# VM_Motor_v06.net
KiCad netlist of a schematic drawn in EAGLE
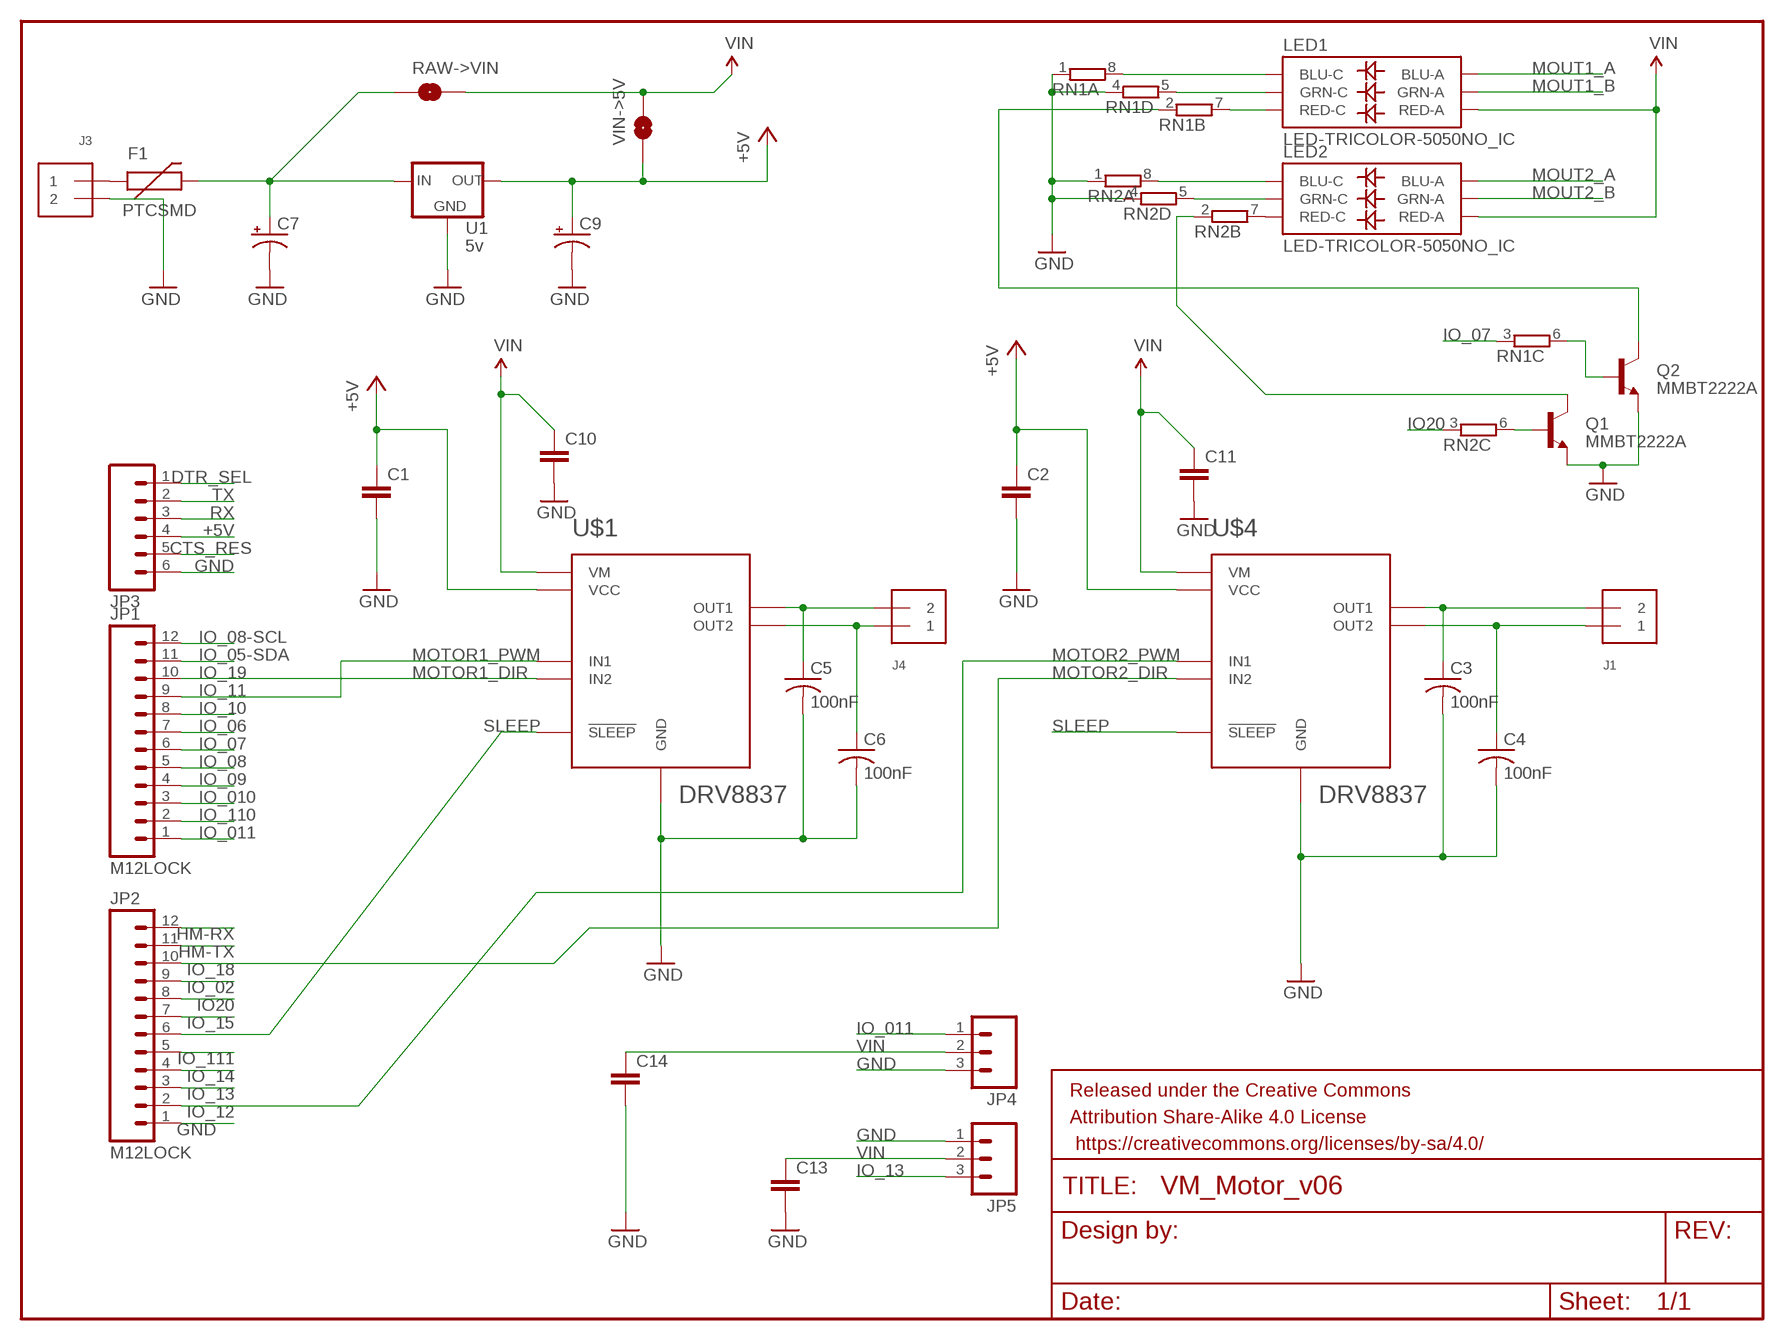
[diagram p0: schematic, sheet 1]

(export (version "E")
  (design (tool "Eeschema 10.0.6"))
  (components
    (comp (ref "C1")
      (value "CAP0402-CAP")
      (footprint "eagle-import:0402-CAP")
      (libsource (lib "eagle-import") (part "CAP0402-CAP"))
    )
    (comp (ref "C2")
      (value "CAP0402-CAP")
      (footprint "eagle-import:0402-CAP")
      (libsource (lib "eagle-import") (part "CAP0402-CAP"))
    )
    (comp (ref "C3")
      (value "100nF")
      (footprint "eagle-import:C0402")
      (libsource (lib "eagle-import") (part "C-USC0402"))
    )
    (comp (ref "C4")
      (value "100nF")
      (footprint "eagle-import:C0402")
      (libsource (lib "eagle-import") (part "C-USC0402"))
    )
    (comp (ref "C5")
      (value "100nF")
      (footprint "eagle-import:C0402")
      (libsource (lib "eagle-import") (part "C-USC0402"))
    )
    (comp (ref "C6")
      (value "100nF")
      (footprint "eagle-import:C0402")
      (libsource (lib "eagle-import") (part "C-USC0402"))
    )
    (comp (ref "C7")
      (value "CPOL-US150CLZ-0810")
      (footprint "eagle-import:150CLZ-0810")
      (libsource (lib "eagle-import") (part "CPOL-US150CLZ-0810"))
    )
    (comp (ref "C9")
      (value "CPOL-US150CLZ-0810")
      (footprint "eagle-import:150CLZ-0810")
      (libsource (lib "eagle-import") (part "CPOL-US150CLZ-0810"))
    )
    (comp (ref "C10")
      (value "CAP0402-CAP")
      (footprint "eagle-import:0402-CAP")
      (libsource (lib "eagle-import") (part "CAP0402-CAP"))
    )
    (comp (ref "C11")
      (value "CAP0402-CAP")
      (footprint "eagle-import:0402-CAP")
      (libsource (lib "eagle-import") (part "CAP0402-CAP"))
    )
    (comp (ref "C13")
      (value "CAP0402-CAP")
      (footprint "eagle-import:0402-CAP")
      (libsource (lib "eagle-import") (part "CAP0402-CAP"))
    )
    (comp (ref "C14")
      (value "CAP0402-CAP")
      (footprint "eagle-import:0402-CAP")
      (libsource (lib "eagle-import") (part "CAP0402-CAP"))
    )
    (comp (ref "F1")
      (value "PTCSMD")
      (footprint "eagle-import:PTC-1206")
      (libsource (lib "eagle-import") (part "PTCSMD"))
    )
    (comp (ref "FRAME1")
      (value "FRAME-LETTER")
      (footprint "eagle-import:CREATIVE_COMMONS")
      (libsource (lib "eagle-import") (part "FRAME-LETTER"))
    )
    (comp (ref "J1")
      (value "TERMBLOCK_1X2")
      (footprint "eagle-import:TERMBLOCK_1X2-3.5MM")
      (libsource (lib "eagle-import") (part "TERMBLOCK_1X2"))
    )
    (comp (ref "J3")
      (value "TERMBLOCK_1X2")
      (footprint "eagle-import:TERMBLOCK_1X2-3.5MM")
      (libsource (lib "eagle-import") (part "TERMBLOCK_1X2"))
    )
    (comp (ref "J4")
      (value "TERMBLOCK_1X2")
      (footprint "eagle-import:TERMBLOCK_1X2-3.5MM")
      (libsource (lib "eagle-import") (part "TERMBLOCK_1X2"))
    )
    (comp (ref "JP1")
      (value "M12LOCK")
      (footprint "eagle-import:1X12_LOCK")
      (libsource (lib "eagle-import") (part "M12LOCK"))
    )
    (comp (ref "JP2")
      (value "M12LOCK")
      (footprint "eagle-import:1X12_LOCK")
      (libsource (lib "eagle-import") (part "M12LOCK"))
    )
    (comp (ref "JP3")
      (value "M06LOCK")
      (footprint "eagle-import:1X06_LOCK")
      (libsource (lib "eagle-import") (part "M06LOCK"))
    )
    (comp (ref "JP4")
      (value "M03LOCK")
      (footprint "eagle-import:1X03_LOCK")
      (libsource (lib "eagle-import") (part "M03LOCK"))
    )
    (comp (ref "JP5")
      (value "M03LOCK")
      (footprint "eagle-import:1X03_LOCK")
      (libsource (lib "eagle-import") (part "M03LOCK"))
    )
    (comp (ref "LED1")
      (value "LED-TRICOLOR-5050NO_IC")
      (footprint "eagle-import:LED-TRICOLOR-5050")
      (libsource (lib "eagle-import") (part "LED-TRICOLOR-5050NO_IC"))
    )
    (comp (ref "LED2")
      (value "LED-TRICOLOR-5050NO_IC")
      (footprint "eagle-import:LED-TRICOLOR-5050")
      (libsource (lib "eagle-import") (part "LED-TRICOLOR-5050NO_IC"))
    )
    (comp (ref "Q1")
      (value "MMBT2222A")
      (footprint "eagle-import:SOT23-3")
      (libsource (lib "eagle-import") (part "TRANSISTOR_NPNMMBT2222A"))
    )
    (comp (ref "Q2")
      (value "MMBT2222A")
      (footprint "eagle-import:SOT23-3")
      (libsource (lib "eagle-import") (part "TRANSISTOR_NPNMMBT2222A"))
    )
    (comp (ref "RAW->VIN")
      (value "SOLDERJUMPERNO")
      (footprint "eagle-import:SJ_2S-NO")
      (libsource (lib "eagle-import") (part "SOLDERJUMPERNO"))
    )
    (comp (ref "RN1")
      (value "4R-N0402ARV341")
      (footprint "eagle-import:4X0402ARV341")
      (libsource (lib "eagle-import") (part "4R-N0402ARV341"))
    )
    (comp (ref "RN2")
      (value "4R-N0402ARV341")
      (footprint "eagle-import:4X0402ARV341")
      (libsource (lib "eagle-import") (part "4R-N0402ARV341"))
    )
    (comp (ref "U$1")
      (value "DRV8837")
      (footprint "eagle-import:QFN8")
      (libsource (lib "eagle-import") (part "DRV8837"))
    )
    (comp (ref "U$4")
      (value "DRV8837")
      (footprint "eagle-import:QFN8")
      (libsource (lib "eagle-import") (part "DRV8837"))
    )
    (comp (ref "U1")
      (value "5v")
      (footprint "eagle-import:DPAK")
      (libsource (lib "eagle-import") (part "V_REG_MC33269DT"))
    )
    (comp (ref "VIN->5V")
      (value "SOLDERJUMPERNO")
      (footprint "eagle-import:SJ_2S-NO")
      (libsource (lib "eagle-import") (part "SOLDERJUMPERNO"))
    )
  )
  (nets
    (net (code "1") (name "+5V") (class "Default")
      (node (ref "C1") (pin "1") (pinfunction "1_1") (pintype "passive"))
      (node (ref "C2") (pin "1") (pinfunction "1_1") (pintype "passive"))
      (node (ref "C9") (pin "+") (pinfunction "+_+") (pintype "passive"))
      (node (ref "JP3") (pin "4") (pinfunction "4_4") (pintype "passive"))
      (node (ref "U$1") (pin "P$8") (pinfunction "VCC_P$8") (pintype "bidirectional"))
      (node (ref "U$4") (pin "P$8") (pinfunction "VCC_P$8") (pintype "bidirectional"))
      (node (ref "U1") (pin "4") (pinfunction "OUT_4") (pintype "output"))
      (node (ref "VIN->5V") (pin "1") (pinfunction "1_1") (pintype "passive"))
    )
    (net (code "2") (name "/CTS_RES") (class "Default")
      (node (ref "JP3") (pin "5") (pinfunction "5_5") (pintype "passive"))
    )
    (net (code "3") (name "/DTR_SEL") (class "Default")
      (node (ref "JP3") (pin "1") (pinfunction "1_1") (pintype "passive"))
    )
    (net (code "4") (name "/HM-RX") (class "Default")
      (node (ref "JP2") (pin "12") (pinfunction "12_12") (pintype "passive"))
    )
    (net (code "5") (name "/HM-TX") (class "Default")
      (node (ref "JP2") (pin "11") (pinfunction "11_11") (pintype "passive"))
    )
    (net (code "6") (name "/IO20") (class "Default")
      (node (ref "JP2") (pin "8") (pinfunction "8_8") (pintype "passive"))
      (node (ref "RN2") (pin "3") (pinfunction "1_3") (pintype "passive"))
    )
    (net (code "7") (name "/IO_02") (class "Default")
      (node (ref "JP2") (pin "9") (pinfunction "9_9") (pintype "passive"))
    )
    (net (code "8") (name "/IO_05-SDA") (class "Default")
      (node (ref "JP1") (pin "11") (pinfunction "11_11") (pintype "passive"))
    )
    (net (code "9") (name "/IO_06") (class "Default")
      (node (ref "JP1") (pin "7") (pinfunction "7_7") (pintype "passive"))
    )
    (net (code "10") (name "/IO_07") (class "Default")
      (node (ref "JP1") (pin "6") (pinfunction "6_6") (pintype "passive"))
      (node (ref "RN1") (pin "3") (pinfunction "1_3") (pintype "passive"))
    )
    (net (code "11") (name "/IO_08") (class "Default")
      (node (ref "JP1") (pin "5") (pinfunction "5_5") (pintype "passive"))
    )
    (net (code "12") (name "/IO_08-SCL") (class "Default")
      (node (ref "JP1") (pin "12") (pinfunction "12_12") (pintype "passive"))
    )
    (net (code "13") (name "/IO_09") (class "Default")
      (node (ref "JP1") (pin "4") (pinfunction "4_4") (pintype "passive"))
    )
    (net (code "14") (name "/IO_10") (class "Default")
      (node (ref "JP1") (pin "8") (pinfunction "8_8") (pintype "passive"))
    )
    (net (code "15") (name "/IO_010") (class "Default")
      (node (ref "JP1") (pin "3") (pinfunction "3_3") (pintype "passive"))
    )
    (net (code "16") (name "/IO_011") (class "Default")
      (node (ref "JP1") (pin "1") (pinfunction "1_1") (pintype "passive"))
      (node (ref "JP4") (pin "1") (pinfunction "1_1") (pintype "passive"))
    )
    (net (code "17") (name "/IO_13") (class "Default")
      (node (ref "JP2") (pin "3") (pinfunction "3_3") (pintype "passive"))
      (node (ref "JP5") (pin "3") (pinfunction "3_3") (pintype "passive"))
    )
    (net (code "18") (name "/IO_14") (class "Default")
      (node (ref "JP2") (pin "4") (pinfunction "4_4") (pintype "passive"))
    )
    (net (code "19") (name "/IO_15") (class "Default")
      (node (ref "JP2") (pin "7") (pinfunction "7_7") (pintype "passive"))
    )
    (net (code "20") (name "/IO_110") (class "Default")
      (node (ref "JP1") (pin "2") (pinfunction "2_2") (pintype "passive"))
    )
    (net (code "21") (name "/IO_111") (class "Default")
      (node (ref "JP2") (pin "5") (pinfunction "5_5") (pintype "passive"))
    )
    (net (code "22") (name "/MOTOR1_DIR") (class "Default")
      (node (ref "JP1") (pin "10") (pinfunction "10_10") (pintype "passive"))
      (node (ref "U$1") (pin "P$5") (pinfunction "IN2_P$5") (pintype "bidirectional"))
    )
    (net (code "23") (name "/MOTOR1_PWM") (class "Default")
      (node (ref "JP1") (pin "9") (pinfunction "9_9") (pintype "passive"))
      (node (ref "U$1") (pin "P$6") (pinfunction "IN1_P$6") (pintype "bidirectional"))
    )
    (net (code "24") (name "/MOTOR2_DIR") (class "Default")
      (node (ref "JP2") (pin "10") (pinfunction "10_10") (pintype "passive"))
      (node (ref "U$4") (pin "P$5") (pinfunction "IN2_P$5") (pintype "bidirectional"))
    )
    (net (code "25") (name "/MOTOR2_PWM") (class "Default")
      (node (ref "JP2") (pin "2") (pinfunction "2_2") (pintype "passive"))
      (node (ref "U$4") (pin "P$6") (pinfunction "IN1_P$6") (pintype "bidirectional"))
    )
    (net (code "26") (name "/MOUT1_A") (class "Default")
      (node (ref "C5") (pin "1") (pinfunction "1_1") (pintype "passive"))
      (node (ref "J4") (pin "2") (pinfunction "2_2") (pintype "passive"))
      (node (ref "LED1") (pin "3") (pinfunction "BLU-A_3") (pintype "bidirectional"))
      (node (ref "U$1") (pin "P$2") (pinfunction "OUT1_P$2") (pintype "bidirectional"))
    )
    (net (code "27") (name "/MOUT1_B") (class "Default")
      (node (ref "C6") (pin "1") (pinfunction "1_1") (pintype "passive"))
      (node (ref "J4") (pin "1") (pinfunction "1_1") (pintype "passive"))
      (node (ref "LED1") (pin "1") (pinfunction "GRN-A_1") (pintype "bidirectional"))
      (node (ref "U$1") (pin "P$3") (pinfunction "OUT2_P$3") (pintype "bidirectional"))
    )
    (net (code "28") (name "/MOUT2_A") (class "Default")
      (node (ref "C3") (pin "1") (pinfunction "1_1") (pintype "passive"))
      (node (ref "J1") (pin "2") (pinfunction "2_2") (pintype "passive"))
      (node (ref "LED2") (pin "3") (pinfunction "BLU-A_3") (pintype "bidirectional"))
      (node (ref "U$4") (pin "P$2") (pinfunction "OUT1_P$2") (pintype "bidirectional"))
    )
    (net (code "29") (name "/MOUT2_B") (class "Default")
      (node (ref "C4") (pin "1") (pinfunction "1_1") (pintype "passive"))
      (node (ref "J1") (pin "1") (pinfunction "1_1") (pintype "passive"))
      (node (ref "LED2") (pin "1") (pinfunction "GRN-A_1") (pintype "bidirectional"))
      (node (ref "U$4") (pin "P$3") (pinfunction "OUT2_P$3") (pintype "bidirectional"))
    )
    (net (code "30") (name "/RX") (class "Default")
      (node (ref "JP3") (pin "3") (pinfunction "3_3") (pintype "passive"))
    )
    (net (code "31") (name "/SLEEP") (class "Default")
      (node (ref "JP2") (pin "6") (pinfunction "6_6") (pintype "passive"))
      (node (ref "U$1") (pin "P$7") (pinfunction "~{SLEEP}_P$7") (pintype "bidirectional"))
      (node (ref "U$4") (pin "P$7") (pinfunction "~{SLEEP}_P$7") (pintype "bidirectional"))
    )
    (net (code "32") (name "/TX") (class "Default")
      (node (ref "JP3") (pin "2") (pinfunction "2_2") (pintype "passive"))
    )
    (net (code "33") (name "GND") (class "Default")
      (node (ref "C1") (pin "2") (pinfunction "2_2") (pintype "passive"))
      (node (ref "C10") (pin "2") (pinfunction "2_2") (pintype "passive"))
      (node (ref "C11") (pin "2") (pinfunction "2_2") (pintype "passive"))
      (node (ref "C13") (pin "2") (pinfunction "2_2") (pintype "passive"))
      (node (ref "C14") (pin "2") (pinfunction "2_2") (pintype "passive"))
      (node (ref "C2") (pin "2") (pinfunction "2_2") (pintype "passive"))
      (node (ref "C3") (pin "2") (pinfunction "2_2") (pintype "passive"))
      (node (ref "C4") (pin "2") (pinfunction "2_2") (pintype "passive"))
      (node (ref "C5") (pin "2") (pinfunction "2_2") (pintype "passive"))
      (node (ref "C6") (pin "2") (pinfunction "2_2") (pintype "passive"))
      (node (ref "C7") (pin "-") (pinfunction "-_-") (pintype "passive"))
      (node (ref "C9") (pin "-") (pinfunction "-_-") (pintype "passive"))
      (node (ref "J3") (pin "2") (pinfunction "2_2") (pintype "passive"))
      (node (ref "JP2") (pin "1") (pinfunction "1_1") (pintype "passive"))
      (node (ref "JP3") (pin "6") (pinfunction "6_6") (pintype "passive"))
      (node (ref "JP4") (pin "3") (pinfunction "3_3") (pintype "passive"))
      (node (ref "JP5") (pin "1") (pinfunction "1_1") (pintype "passive"))
      (node (ref "Q1") (pin "2") (pinfunction "E_2") (pintype "passive"))
      (node (ref "Q2") (pin "2") (pinfunction "E_2") (pintype "passive"))
      (node (ref "RN1") (pin "1") (pinfunction "1_1") (pintype "passive"))
      (node (ref "RN1") (pin "4") (pinfunction "1_4") (pintype "passive"))
      (node (ref "RN2") (pin "1") (pinfunction "1_1") (pintype "passive"))
      (node (ref "RN2") (pin "4") (pinfunction "1_4") (pintype "passive"))
      (node (ref "U$1") (pin "P$10") (pinfunction "GND_P$10") (pintype "bidirectional"))
      (node (ref "U$1") (pin "P$11") (pinfunction "GND_P$11") (pintype "bidirectional"))
      (node (ref "U$1") (pin "P$4") (pinfunction "GND_P$4") (pintype "bidirectional"))
      (node (ref "U$1") (pin "P$9") (pinfunction "GND_P$9") (pintype "bidirectional"))
      (node (ref "U$4") (pin "P$10") (pinfunction "GND_P$10") (pintype "bidirectional"))
      (node (ref "U$4") (pin "P$11") (pinfunction "GND_P$11") (pintype "bidirectional"))
      (node (ref "U$4") (pin "P$4") (pinfunction "GND_P$4") (pintype "bidirectional"))
      (node (ref "U$4") (pin "P$9") (pinfunction "GND_P$9") (pintype "bidirectional"))
      (node (ref "U1") (pin "1") (pinfunction "GND_1") (pintype "input"))
    )
    (net (code "34") (name "Net-(F1-Pad1)") (class "Default")
      (node (ref "F1") (pin "1") (pinfunction "1_1") (pintype "bidirectional"))
      (node (ref "J3") (pin "1") (pinfunction "1_1") (pintype "passive"))
    )
    (net (code "35") (name "Net-(LED1-BLU-C)") (class "Default")
      (node (ref "LED1") (pin "4") (pinfunction "BLU-C_4") (pintype "bidirectional"))
      (node (ref "RN1") (pin "8") (pinfunction "2_8") (pintype "passive"))
    )
    (net (code "36") (name "Net-(LED1-GRN-C)") (class "Default")
      (node (ref "LED1") (pin "6") (pinfunction "GRN-C_6") (pintype "bidirectional"))
      (node (ref "RN1") (pin "5") (pinfunction "2_5") (pintype "passive"))
    )
    (net (code "37") (name "Net-(LED1-RED-C)") (class "Default")
      (node (ref "LED1") (pin "5") (pinfunction "RED-C_5") (pintype "bidirectional"))
      (node (ref "RN1") (pin "7") (pinfunction "2_7") (pintype "passive"))
    )
    (net (code "38") (name "Net-(LED2-BLU-C)") (class "Default")
      (node (ref "LED2") (pin "4") (pinfunction "BLU-C_4") (pintype "bidirectional"))
      (node (ref "RN2") (pin "8") (pinfunction "2_8") (pintype "passive"))
    )
    (net (code "39") (name "Net-(LED2-GRN-C)") (class "Default")
      (node (ref "LED2") (pin "6") (pinfunction "GRN-C_6") (pintype "bidirectional"))
      (node (ref "RN2") (pin "5") (pinfunction "2_5") (pintype "passive"))
    )
    (net (code "40") (name "Net-(LED2-RED-C)") (class "Default")
      (node (ref "LED2") (pin "5") (pinfunction "RED-C_5") (pintype "bidirectional"))
      (node (ref "RN2") (pin "7") (pinfunction "2_7") (pintype "passive"))
    )
    (net (code "41") (name "Net-(Q1-B)") (class "Default")
      (node (ref "Q1") (pin "1") (pinfunction "B_1") (pintype "passive"))
      (node (ref "RN2") (pin "6") (pinfunction "2_6") (pintype "passive"))
    )
    (net (code "42") (name "Net-(Q1-C)") (class "Default")
      (node (ref "Q1") (pin "3") (pinfunction "C_3") (pintype "passive"))
      (node (ref "RN2") (pin "2") (pinfunction "1_2") (pintype "passive"))
    )
    (net (code "43") (name "Net-(Q2-B)") (class "Default")
      (node (ref "Q2") (pin "1") (pinfunction "B_1") (pintype "passive"))
      (node (ref "RN1") (pin "6") (pinfunction "2_6") (pintype "passive"))
    )
    (net (code "44") (name "Net-(Q2-C)") (class "Default")
      (node (ref "Q2") (pin "3") (pinfunction "C_3") (pintype "passive"))
      (node (ref "RN1") (pin "2") (pinfunction "1_2") (pintype "passive"))
    )
    (net (code "45") (name "Net-(U1-IN)") (class "Default")
      (node (ref "C7") (pin "+") (pinfunction "+_+") (pintype "passive"))
      (node (ref "F1") (pin "2") (pinfunction "2_2") (pintype "bidirectional"))
      (node (ref "RAW->VIN") (pin "1") (pinfunction "1_1") (pintype "passive"))
      (node (ref "U1") (pin "3") (pinfunction "IN_3") (pintype "input"))
    )
    (net (code "46") (name "VIN") (class "Default")
      (node (ref "C10") (pin "1") (pinfunction "1_1") (pintype "passive"))
      (node (ref "C11") (pin "1") (pinfunction "1_1") (pintype "passive"))
      (node (ref "C13") (pin "1") (pinfunction "1_1") (pintype "passive"))
      (node (ref "C14") (pin "1") (pinfunction "1_1") (pintype "passive"))
      (node (ref "JP4") (pin "2") (pinfunction "2_2") (pintype "passive"))
      (node (ref "JP5") (pin "2") (pinfunction "2_2") (pintype "passive"))
      (node (ref "LED1") (pin "2") (pinfunction "RED-A_2") (pintype "bidirectional"))
      (node (ref "LED2") (pin "2") (pinfunction "RED-A_2") (pintype "bidirectional"))
      (node (ref "RAW->VIN") (pin "2") (pinfunction "2_2") (pintype "passive"))
      (node (ref "U$1") (pin "P$1") (pinfunction "VM_P$1") (pintype "bidirectional"))
      (node (ref "U$4") (pin "P$1") (pinfunction "VM_P$1") (pintype "bidirectional"))
      (node (ref "VIN->5V") (pin "2") (pinfunction "2_2") (pintype "passive"))
    )
  )
)
